# I2C_DP_Sensor_1.net
KiCad netlist of a schematic drawn in Altium Designer
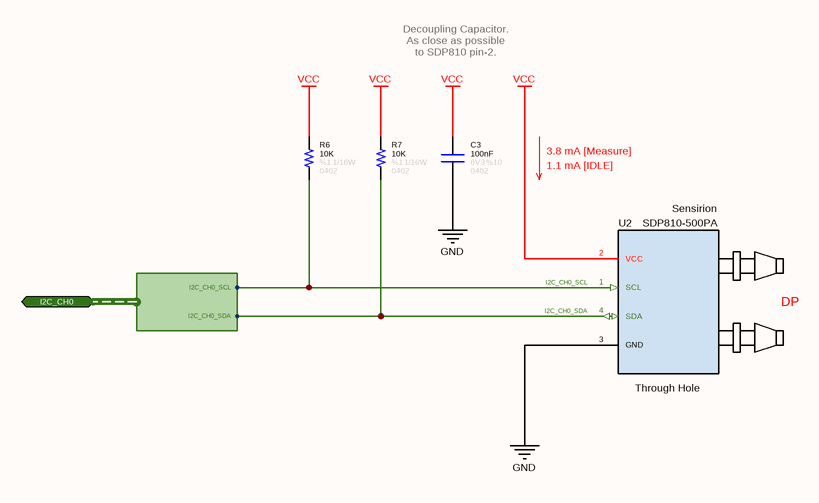
[diagram p0: I2C DP Sensor 1.SchDoc]

(export (version "E")
  (design (tool "Eeschema 10.0.6"))
  (components
    (comp (ref "C3")
      (value "100nF")
      (footprint "CAPACITOR_0402")
      (description "Capacitor - 100nF [0402-6V3] (Ceramic)")
      (fields
        (field (name "MANUFACTURER PART NUMBER") "04026D104KAT4A")
        (field (name "TOLERANCE") "%10")
        (field (name "VOLTAGE") "6V3")
        (field (name "CASE") "0402")
        (field (name "Comment") "Capacitor - 100nF [0402] (Ceramic)")
      )
      (libsource (lib "P101DA_Library") (part "Capacitor - 100nF [0402-6V3]"))
    )
    (comp (ref "R6")
      (value "10K")
      (footprint "RESISTOR_0402")
      (description "Thick Film Resistors - SMD 1/16 W 10 KOhm 1%")
      (fields
        (field (name "MANUFACTURER PART NUMBER") "CRCW040210K0FKED")
        (field (name "TOLERANCE") "%1")
        (field (name "CASE") "0402")
        (field (name "POWER") "1/16W")
        (field (name "Comment") "10K - 0402 - %1 - 1/16W")
      )
      (libsource (lib "P101DA_Library") (part "Resistor - 10K [0402]"))
    )
    (comp (ref "R7")
      (value "10K")
      (footprint "RESISTOR_0402")
      (description "Thick Film Resistors - SMD 1/16 W 10 KOhm 1%")
      (fields
        (field (name "MANUFACTURER PART NUMBER") "CRCW040210K0FKED")
        (field (name "TOLERANCE") "%1")
        (field (name "CASE") "0402")
        (field (name "POWER") "1/16W")
        (field (name "Comment") "10K - 0402 - %1 - 1/16W")
      )
      (libsource (lib "P101DA_Library") (part "Resistor - 10K [0402]"))
    )
    (comp (ref "U2")
      (value "SDP810-500PA")
      (footprint "SDP810-500PA")
      (description "Board Mount Pressure Sensors Tube Connection, I2C , 500Pa")
      (fields
        (field (name "MANUFACTURER NAME") "Sensirion")
        (field (name "MANUFACTURER PART NUMBER") "SDP810-500PA")
        (field (name "CASE") "Through Hole")
      )
      (libsource (lib "P101DA_Library") (part "IC - SDP810-500PA"))
    )
  )
  (nets
    (net (code "2") (name "/I2C_CH0_SCL") (class "Default")
      (node (ref "R6") (pin "1") (pinfunction "1_1") (pintype "passive"))
      (node (ref "U2") (pin "1") (pinfunction "SCL_1") (pintype "input"))
    )
    (net (code "3") (name "/I2C_CH0_SDA") (class "Default")
      (node (ref "R7") (pin "1") (pinfunction "1_1") (pintype "passive"))
      (node (ref "U2") (pin "4") (pinfunction "SDA_4") (pintype "bidirectional"))
    )
    (net (code "5") (name "GND") (class "Default")
      (node (ref "C3") (pin "1") (pinfunction "1_1") (pintype "passive"))
      (node (ref "U2") (pin "3") (pinfunction "GND_3") (pintype "passive"))
    )
    (net (code "6") (name "VCC") (class "Default")
      (node (ref "C3") (pin "2") (pinfunction "2_2") (pintype "passive"))
      (node (ref "R6") (pin "2") (pinfunction "2_2") (pintype "passive"))
      (node (ref "R7") (pin "2") (pinfunction "2_2") (pintype "passive"))
      (node (ref "U2") (pin "2") (pinfunction "VCC_2") (pintype "power_in"))
    )
  )
)
